# Reaccion-vRegvB.net
KiCad netlist of a schematic drawn in EAGLE
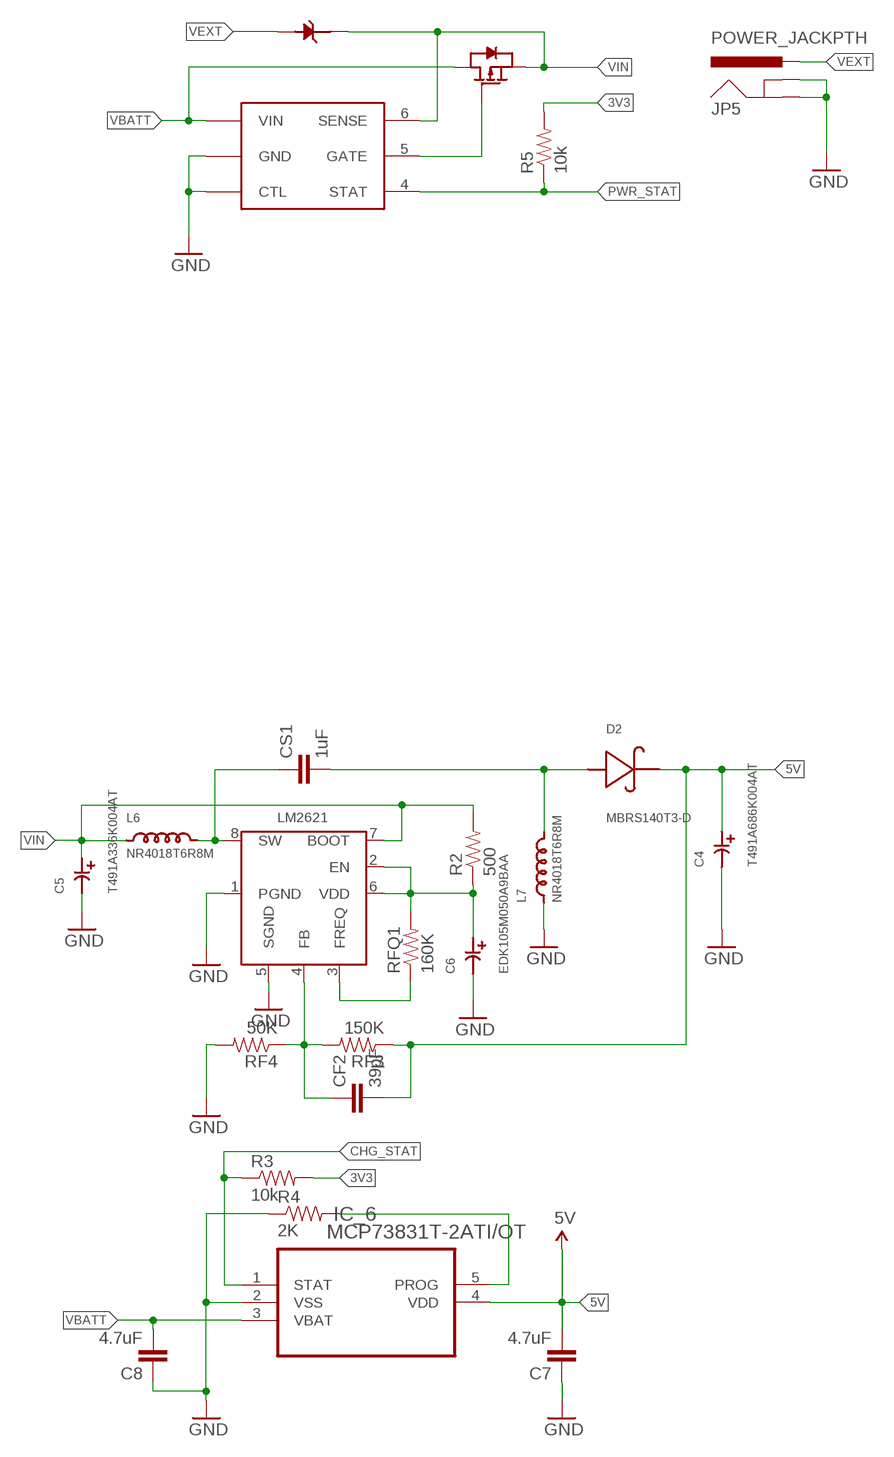
[diagram p0: schematic, sheet 1]

(export (version "E")
  (design (tool "Eeschema 10.0.6"))
  (components
    (comp (ref "C4")
      (value "T491A686K004AT")
      (footprint "eagle-import:3216-18")
      (libsource (lib "eagle-import") (part "T491A686K004AT"))
    )
    (comp (ref "C5")
      (value "T491A336K004AT")
      (footprint "eagle-import:3216-18")
      (libsource (lib "eagle-import") (part "T491A336K004AT"))
    )
    (comp (ref "C6")
      (value "EDK105M050A9BAA")
      (footprint "eagle-import:EDK105M050A9BAA")
      (libsource (lib "eagle-import") (part "EDK105M050A9BAA"))
    )
    (comp (ref "C7")
      (value "4.7uF")
      (footprint "eagle-import:0805")
      (libsource (lib "eagle-import") (part "CAP0805"))
    )
    (comp (ref "C8")
      (value "4.7uF")
      (footprint "eagle-import:0805")
      (libsource (lib "eagle-import") (part "CAP0805"))
    )
    (comp (ref "CF2")
      (value "39pF")
      (footprint "eagle-import:0805")
      (libsource (lib "eagle-import") (part "CAP0805"))
    )
    (comp (ref "CS1")
      (value "1uF")
      (footprint "eagle-import:0805")
      (libsource (lib "eagle-import") (part "CAP0805"))
    )
    (comp (ref "D2")
      (value "MBRS140T3-D")
      (footprint "eagle-import:MBRS140T3G")
      (libsource (lib "eagle-import") (part "MBRS140T3-D"))
    )
    (comp (ref "D4")
      (value "1N5819HW-7-F")
      (footprint "eagle-import:SOD123")
      (libsource (lib "eagle-import") (part "1N5819HW-7-F"))
    )
    (comp (ref "IC_1")
      (value "LTC4412")
      (footprint "eagle-import:SOT23-6L")
      (libsource (lib "eagle-import") (part "LTC4412"))
    )
    (comp (ref "IC_4")
      (value "LM2621")
      (footprint "eagle-import:R-PDSO-G8")
      (libsource (lib "eagle-import") (part "LM2621"))
    )
    (comp (ref "IC_6")
      (value "MCP73831T-2ATI/OT")
      (footprint "eagle-import:SOT95P300X145-5N")
      (libsource (lib "eagle-import") (part "MCP73831T-2ATI/OT"))
    )
    (comp (ref "JP5")
      (value "POWER_JACKPTH")
      (footprint "eagle-import:POWER_JACK_PTH")
      (libsource (lib "eagle-import") (part "POWER_JACKPTH"))
    )
    (comp (ref "L6")
      (value "NR4018T6R8M")
      (footprint "eagle-import:NR4018_NRS4018")
      (libsource (lib "eagle-import") (part "NR4018T6R8M"))
    )
    (comp (ref "L7")
      (value "NR4018T6R8M")
      (footprint "eagle-import:NR4018_NRS4018")
      (libsource (lib "eagle-import") (part "NR4018T6R8M"))
    )
    (comp (ref "Q9")
      (value "SI2301CDS")
      (footprint "eagle-import:SOT23")
      (libsource (lib "eagle-import") (part "SI2301CDS"))
    )
    (comp (ref "R2")
      (value "500")
      (footprint "eagle-import:0805")
      (libsource (lib "eagle-import") (part "RESISTOR0805-RES"))
    )
    (comp (ref "R3")
      (value "10k")
      (footprint "eagle-import:0805")
      (libsource (lib "eagle-import") (part "RESISTOR0805-RES"))
    )
    (comp (ref "R4")
      (value "2K")
      (footprint "eagle-import:0805")
      (libsource (lib "eagle-import") (part "RESISTOR0805-RES"))
    )
    (comp (ref "R5")
      (value "10k")
      (footprint "eagle-import:0805")
      (libsource (lib "eagle-import") (part "RESISTOR0805-RES"))
    )
    (comp (ref "RF3")
      (value "150K")
      (footprint "eagle-import:0805")
      (libsource (lib "eagle-import") (part "RESISTOR0805-RES"))
    )
    (comp (ref "RF4")
      (value "50K")
      (footprint "eagle-import:0805")
      (libsource (lib "eagle-import") (part "RESISTOR0805-RES"))
    )
    (comp (ref "RFQ1")
      (value "160K")
      (footprint "eagle-import:0805")
      (libsource (lib "eagle-import") (part "RESISTOR0805-RES"))
    )
  )
  (nets
    (net (code "1") (name "3V3") (class "Default")
      (node (ref "R3") (pin "2") (pinfunction "2_2") (pintype "passive"))
      (node (ref "R5") (pin "2") (pinfunction "2_2") (pintype "passive"))
    )
    (net (code "2") (name "5V") (class "Default")
      (node (ref "C4") (pin "1") (pinfunction "P$1_1") (pintype "bidirectional"))
      (node (ref "C7") (pin "2") (pinfunction "2_2") (pintype "passive"))
      (node (ref "CF2") (pin "2") (pinfunction "2_2") (pintype "passive"))
      (node (ref "D2") (pin "2") (pinfunction "2_2") (pintype "bidirectional"))
      (node (ref "IC_6") (pin "4") (pinfunction "VDD_4") (pintype "power_in"))
      (node (ref "RF3") (pin "1") (pinfunction "1_1") (pintype "passive"))
    )
    (net (code "3") (name "CHG_STAT") (class "Default")
      (node (ref "IC_6") (pin "1") (pinfunction "STAT_1") (pintype "input"))
      (node (ref "R3") (pin "1") (pinfunction "1_1") (pintype "passive"))
    )
    (net (code "4") (name "GND") (class "Default")
      (node (ref "C4") (pin "2") (pinfunction "P$2_2") (pintype "bidirectional"))
      (node (ref "C5") (pin "2") (pinfunction "P$2_2") (pintype "bidirectional"))
      (node (ref "C6") (pin "P$2") (pinfunction "P$2_P$2") (pintype "bidirectional"))
      (node (ref "C7") (pin "1") (pinfunction "1_1") (pintype "passive"))
      (node (ref "C8") (pin "1") (pinfunction "1_1") (pintype "passive"))
      (node (ref "IC_1") (pin "2") (pinfunction "GND_2") (pintype "power_in"))
      (node (ref "IC_1") (pin "3") (pinfunction "CTL_3") (pintype "input"))
      (node (ref "IC_4") (pin "1") (pinfunction "PGND_1") (pintype "bidirectional"))
      (node (ref "IC_4") (pin "5") (pinfunction "SGND_5") (pintype "bidirectional"))
      (node (ref "IC_6") (pin "2") (pinfunction "VSS_2") (pintype "passive"))
      (node (ref "JP5") (pin "GND") (pinfunction "GND_GND") (pintype "bidirectional"))
      (node (ref "JP5") (pin "GNDBREAK") (pinfunction "GNDBREAK_GNDBREAK") (pintype "bidirectional"))
      (node (ref "L7") (pin "P$1") (pinfunction "P$1_P$1") (pintype "bidirectional"))
      (node (ref "R4") (pin "1") (pinfunction "1_1") (pintype "passive"))
      (node (ref "RF4") (pin "2") (pinfunction "2_2") (pintype "passive"))
    )
    (net (code "5") (name "Net-(CS1-Pad2)") (class "Default")
      (node (ref "CS1") (pin "2") (pinfunction "2_2") (pintype "passive"))
      (node (ref "D2") (pin "1") (pinfunction "1_1") (pintype "bidirectional"))
      (node (ref "L7") (pin "P$2") (pinfunction "P$2_P$2") (pintype "bidirectional"))
    )
    (net (code "6") (name "Net-(IC_1-GATE)") (class "Default")
      (node (ref "IC_1") (pin "5") (pinfunction "GATE_5") (pintype "output"))
      (node (ref "Q9") (pin "1") (pinfunction "GATE_1") (pintype "passive"))
    )
    (net (code "7") (name "Net-(IC_4-EN)") (class "Default")
      (node (ref "C6") (pin "P$1") (pinfunction "P$1_P$1") (pintype "bidirectional"))
      (node (ref "IC_4") (pin "2") (pinfunction "EN_2") (pintype "bidirectional"))
      (node (ref "IC_4") (pin "6") (pinfunction "VDD_6") (pintype "bidirectional"))
      (node (ref "R2") (pin "1") (pinfunction "1_1") (pintype "passive"))
      (node (ref "RFQ1") (pin "2") (pinfunction "2_2") (pintype "passive"))
    )
    (net (code "8") (name "Net-(IC_4-FB)") (class "Default")
      (node (ref "CF2") (pin "1") (pinfunction "1_1") (pintype "passive"))
      (node (ref "IC_4") (pin "4") (pinfunction "FB_4") (pintype "bidirectional"))
      (node (ref "RF3") (pin "2") (pinfunction "2_2") (pintype "passive"))
      (node (ref "RF4") (pin "1") (pinfunction "1_1") (pintype "passive"))
    )
    (net (code "9") (name "Net-(IC_4-FREQ)") (class "Default")
      (node (ref "IC_4") (pin "3") (pinfunction "FREQ_3") (pintype "bidirectional"))
      (node (ref "RFQ1") (pin "1") (pinfunction "1_1") (pintype "passive"))
    )
    (net (code "10") (name "Net-(IC_4-SW)") (class "Default")
      (node (ref "CS1") (pin "1") (pinfunction "1_1") (pintype "passive"))
      (node (ref "IC_4") (pin "8") (pinfunction "SW_8") (pintype "bidirectional"))
      (node (ref "L6") (pin "P$2") (pinfunction "P$2_P$2") (pintype "bidirectional"))
    )
    (net (code "11") (name "Net-(IC_6-PROG)") (class "Default")
      (node (ref "IC_6") (pin "5") (pinfunction "PROG_5") (pintype "input"))
      (node (ref "R4") (pin "2") (pinfunction "2_2") (pintype "passive"))
    )
    (net (code "12") (name "PWR_STAT") (class "Default")
      (node (ref "IC_1") (pin "4") (pinfunction "STAT_4") (pintype "output"))
      (node (ref "R5") (pin "1") (pinfunction "1_1") (pintype "passive"))
    )
    (net (code "13") (name "VBATT") (class "Default")
      (node (ref "C8") (pin "2") (pinfunction "2_2") (pintype "passive"))
      (node (ref "IC_1") (pin "1") (pinfunction "VIN_1") (pintype "power_in"))
      (node (ref "IC_6") (pin "3") (pinfunction "VBAT_3") (pintype "input"))
      (node (ref "Q9") (pin "3") (pinfunction "DRAIN_3") (pintype "passive"))
    )
    (net (code "14") (name "VEXT") (class "Default")
      (node (ref "D4") (pin "2") (pinfunction "ANODE_2") (pintype "passive"))
      (node (ref "JP5") (pin "PWR") (pinfunction "PWR_PWR") (pintype "bidirectional"))
    )
    (net (code "15") (name "VIN") (class "Default")
      (node (ref "C5") (pin "1") (pinfunction "P$1_1") (pintype "bidirectional"))
      (node (ref "D4") (pin "1") (pinfunction "CATHODE_1") (pintype "passive"))
      (node (ref "IC_1") (pin "6") (pinfunction "SENSE_6") (pintype "input"))
      (node (ref "IC_4") (pin "7") (pinfunction "BOOT_7") (pintype "bidirectional"))
      (node (ref "L6") (pin "P$1") (pinfunction "P$1_P$1") (pintype "bidirectional"))
      (node (ref "Q9") (pin "2") (pinfunction "SOURCE_2") (pintype "passive"))
      (node (ref "R2") (pin "2") (pinfunction "2_2") (pintype "passive"))
    )
  )
)
